# design.net
KiCad netlist of a schematic drawn in Altium Designer
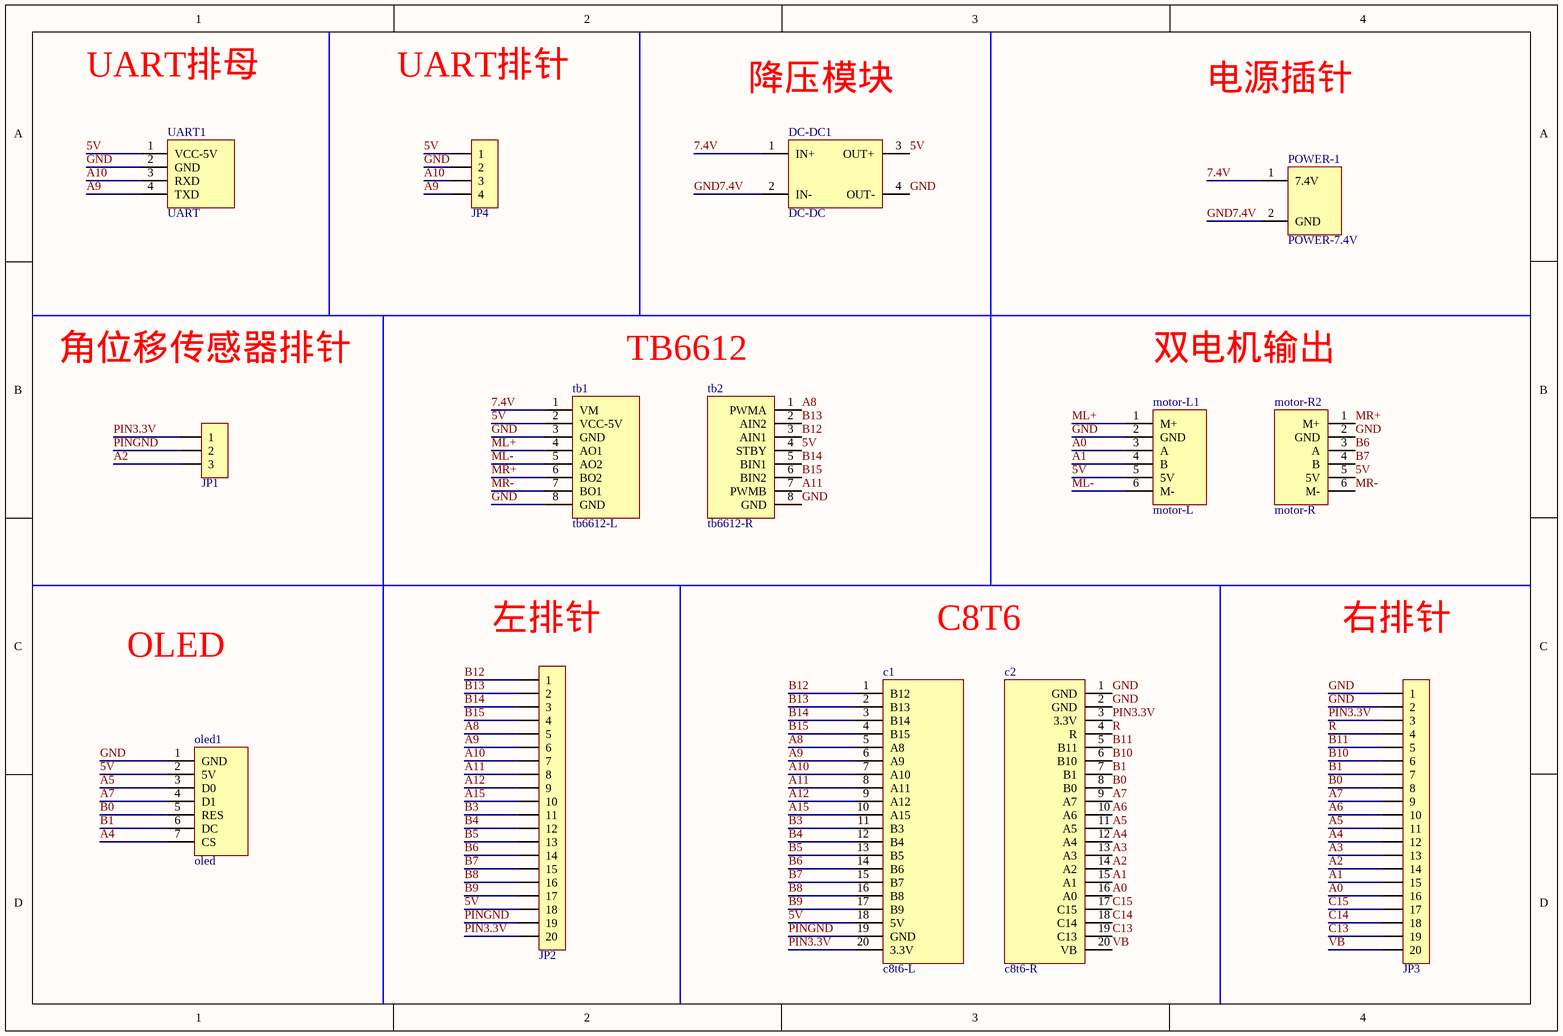
[diagram p0: 倒立摆原理图.SchDoc]

(export (version "E")
  (design (tool "Eeschema 10.0.6"))
  (components
    (comp (ref "c1") (value "c8t6-L") (footprint "HDR2.54-M-LI-20P") (libsource (lib "平衡车") (part "c8t6-L")))
    (comp (ref "c2") (value "c8t6-R") (footprint "HDR2.54-M-LI-20P") (libsource (lib "平衡车") (part "c8t6-R")))
    (comp (ref "DC-DC1") (value "DC-DC") (footprint "DC-DC") (libsource (lib "平衡车") (part "DC-DC")))
    (comp (ref "JP1")
      (value "HDR-1X3")
      (footprint "HDR2.54-LI-3P")
      (description "3P接插件")
      (libsource (lib "5.5 - 2.54mm连接器(KF2EDGK_XH2.54_2.54排针排母)") (part "Header 3"))
    )
    (comp (ref "JP2")
      (value "HDR-1X20")
      (footprint "HDR2.54-LI-20P")
      (description "20P接插件")
      (libsource (lib "5.5 - 2.54mm连接器(KF2EDGK_XH2.54_2.54排针排母)") (part "Header 20"))
    )
    (comp (ref "JP3")
      (value "HDR-1X20")
      (footprint "HDR2.54-LI-20P")
      (description "20P接插件")
      (libsource (lib "5.5 - 2.54mm连接器(KF2EDGK_XH2.54_2.54排针排母)") (part "Header 20"))
    )
    (comp (ref "JP4")
      (value "HDR-1X4")
      (footprint "HDR2.54-LI-4P")
      (description "4P接插件")
      (libsource (lib "5.5 - 2.54mm连接器(KF2EDGK_XH2.54_2.54排针排母)") (part "Header 4"))
    )
    (comp (ref "motor-L1")
      (value "motor-L")
      (footprint "HDR2.54-WI-6P")
      (libsource (lib "平衡车") (part "motor-L"))
    )
    (comp (ref "motor-R2")
      (value "motor-R")
      (footprint "HDR2.54-WI-6P")
      (libsource (lib "平衡车") (part "motor-R"))
    )
    (comp (ref "oled1") (value "oled") (footprint "HDR2.54-M-LI-7P") (libsource (lib "平衡车") (part "oled")))
    (comp (ref "POWER-1")
      (value "POWER-7.4V")
      (footprint "HDR2.54-LI-2P")
      (libsource (lib "平衡车") (part "POWER-7.4V"))
    )
    (comp (ref "tb1")
      (value "tb6612-L")
      (footprint "HDR2.54-M-LI-8P")
      (libsource (lib "平衡车") (part "tb6612-L"))
    )
    (comp (ref "tb2")
      (value "tb6612-R")
      (footprint "HDR2.54-M-LI-8P")
      (libsource (lib "平衡车") (part "tb6612-R"))
    )
    (comp (ref "UART1") (value "UART") (footprint "HDR2.54-M-LI-4P") (libsource (lib "平衡车") (part "UART")))
  )
  (nets
    (net (code "1") (name "/5V") (class "Default")
      (node (ref "DC-DC1") (pin "3") (pinfunction "OUT+_3") (pintype "passive"))
      (node (ref "JP2") (pin "18") (pinfunction "18_18") (pintype "passive"))
      (node (ref "JP4") (pin "1") (pinfunction "1_1") (pintype "passive"))
      (node (ref "UART1") (pin "1") (pinfunction "VCC-5V_1") (pintype "passive"))
      (node (ref "c1") (pin "18") (pinfunction "5V_18") (pintype "passive"))
      (node (ref "motor-L1") (pin "5") (pinfunction "5V_5") (pintype "passive"))
      (node (ref "motor-R2") (pin "5") (pinfunction "5V_5") (pintype "passive"))
      (node (ref "oled1") (pin "2") (pinfunction "5V_2") (pintype "passive"))
      (node (ref "tb1") (pin "2") (pinfunction "VCC-5V_2") (pintype "passive"))
      (node (ref "tb2") (pin "4") (pinfunction "STBY_4") (pintype "passive"))
    )
    (net (code "2") (name "/7.4V") (class "Default")
      (node (ref "DC-DC1") (pin "1") (pinfunction "IN+_1") (pintype "passive"))
      (node (ref "POWER-1") (pin "1") (pinfunction "7.4V_1") (pintype "passive"))
      (node (ref "tb1") (pin "1") (pinfunction "VM_1") (pintype "passive"))
    )
    (net (code "3") (name "/A0") (class "Default")
      (node (ref "JP3") (pin "16") (pinfunction "16_16") (pintype "passive"))
      (node (ref "c2") (pin "16") (pinfunction "A0_16") (pintype "passive"))
      (node (ref "motor-L1") (pin "3") (pinfunction "A_3") (pintype "passive"))
    )
    (net (code "4") (name "/A1") (class "Default")
      (node (ref "JP3") (pin "15") (pinfunction "15_15") (pintype "passive"))
      (node (ref "c2") (pin "15") (pinfunction "A1_15") (pintype "passive"))
      (node (ref "motor-L1") (pin "4") (pinfunction "B_4") (pintype "passive"))
    )
    (net (code "5") (name "/A2") (class "Default")
      (node (ref "JP1") (pin "3") (pinfunction "3_3") (pintype "passive"))
      (node (ref "JP3") (pin "14") (pinfunction "14_14") (pintype "passive"))
      (node (ref "c2") (pin "14") (pinfunction "A2_14") (pintype "passive"))
    )
    (net (code "6") (name "/A3") (class "Default")
      (node (ref "JP3") (pin "13") (pinfunction "13_13") (pintype "passive"))
      (node (ref "c2") (pin "13") (pinfunction "A3_13") (pintype "passive"))
    )
    (net (code "7") (name "/A4") (class "Default")
      (node (ref "JP3") (pin "12") (pinfunction "12_12") (pintype "passive"))
      (node (ref "c2") (pin "12") (pinfunction "A4_12") (pintype "passive"))
      (node (ref "oled1") (pin "7") (pinfunction "CS_7") (pintype "passive"))
    )
    (net (code "8") (name "/A5") (class "Default")
      (node (ref "JP3") (pin "11") (pinfunction "11_11") (pintype "passive"))
      (node (ref "c2") (pin "11") (pinfunction "A5_11") (pintype "passive"))
      (node (ref "oled1") (pin "3") (pinfunction "D0_3") (pintype "passive"))
    )
    (net (code "9") (name "/A6") (class "Default")
      (node (ref "JP3") (pin "10") (pinfunction "10_10") (pintype "passive"))
      (node (ref "c2") (pin "10") (pinfunction "A6_10") (pintype "passive"))
    )
    (net (code "10") (name "/A7") (class "Default")
      (node (ref "JP3") (pin "9") (pinfunction "9_9") (pintype "passive"))
      (node (ref "c2") (pin "9") (pinfunction "A7_9") (pintype "passive"))
      (node (ref "oled1") (pin "4") (pinfunction "D1_4") (pintype "passive"))
    )
    (net (code "11") (name "/A8") (class "Default")
      (node (ref "JP2") (pin "5") (pinfunction "5_5") (pintype "passive"))
      (node (ref "c1") (pin "5") (pinfunction "A8_5") (pintype "passive"))
      (node (ref "tb2") (pin "1") (pinfunction "PWMA_1") (pintype "passive"))
    )
    (net (code "12") (name "/A9") (class "Default")
      (node (ref "JP2") (pin "6") (pinfunction "6_6") (pintype "passive"))
      (node (ref "JP4") (pin "4") (pinfunction "4_4") (pintype "passive"))
      (node (ref "UART1") (pin "4") (pinfunction "TXD_4") (pintype "passive"))
      (node (ref "c1") (pin "6") (pinfunction "A9_6") (pintype "passive"))
    )
    (net (code "13") (name "/A10") (class "Default")
      (node (ref "JP2") (pin "7") (pinfunction "7_7") (pintype "passive"))
      (node (ref "JP4") (pin "3") (pinfunction "3_3") (pintype "passive"))
      (node (ref "UART1") (pin "3") (pinfunction "RXD_3") (pintype "passive"))
      (node (ref "c1") (pin "7") (pinfunction "A10_7") (pintype "passive"))
    )
    (net (code "14") (name "/A11") (class "Default")
      (node (ref "JP2") (pin "8") (pinfunction "8_8") (pintype "passive"))
      (node (ref "c1") (pin "8") (pinfunction "A11_8") (pintype "passive"))
      (node (ref "tb2") (pin "7") (pinfunction "PWMB_7") (pintype "passive"))
    )
    (net (code "15") (name "/A12") (class "Default")
      (node (ref "JP2") (pin "9") (pinfunction "9_9") (pintype "passive"))
      (node (ref "c1") (pin "9") (pinfunction "A12_9") (pintype "passive"))
    )
    (net (code "16") (name "/A15") (class "Default")
      (node (ref "JP2") (pin "10") (pinfunction "10_10") (pintype "passive"))
      (node (ref "c1") (pin "10") (pinfunction "A15_10") (pintype "passive"))
    )
    (net (code "17") (name "/B0") (class "Default")
      (node (ref "JP3") (pin "8") (pinfunction "8_8") (pintype "passive"))
      (node (ref "c2") (pin "8") (pinfunction "B0_8") (pintype "passive"))
      (node (ref "oled1") (pin "5") (pinfunction "RES_5") (pintype "passive"))
    )
    (net (code "18") (name "/B1") (class "Default")
      (node (ref "JP3") (pin "7") (pinfunction "7_7") (pintype "passive"))
      (node (ref "c2") (pin "7") (pinfunction "B1_7") (pintype "passive"))
      (node (ref "oled1") (pin "6") (pinfunction "DC_6") (pintype "passive"))
    )
    (net (code "19") (name "/B3") (class "Default")
      (node (ref "JP2") (pin "11") (pinfunction "11_11") (pintype "passive"))
      (node (ref "c1") (pin "11") (pinfunction "B3_11") (pintype "passive"))
    )
    (net (code "20") (name "/B4") (class "Default")
      (node (ref "JP2") (pin "12") (pinfunction "12_12") (pintype "passive"))
      (node (ref "c1") (pin "12") (pinfunction "B4_12") (pintype "passive"))
    )
    (net (code "21") (name "/B5") (class "Default")
      (node (ref "JP2") (pin "13") (pinfunction "13_13") (pintype "passive"))
      (node (ref "c1") (pin "13") (pinfunction "B5_13") (pintype "passive"))
    )
    (net (code "22") (name "/B6") (class "Default")
      (node (ref "JP2") (pin "14") (pinfunction "14_14") (pintype "passive"))
      (node (ref "c1") (pin "14") (pinfunction "B6_14") (pintype "passive"))
      (node (ref "motor-R2") (pin "3") (pinfunction "A_3") (pintype "passive"))
    )
    (net (code "23") (name "/B7") (class "Default")
      (node (ref "JP2") (pin "15") (pinfunction "15_15") (pintype "passive"))
      (node (ref "c1") (pin "15") (pinfunction "B7_15") (pintype "passive"))
      (node (ref "motor-R2") (pin "4") (pinfunction "B_4") (pintype "passive"))
    )
    (net (code "24") (name "/B8") (class "Default")
      (node (ref "JP2") (pin "16") (pinfunction "16_16") (pintype "passive"))
      (node (ref "c1") (pin "16") (pinfunction "B8_16") (pintype "passive"))
    )
    (net (code "25") (name "/B9") (class "Default")
      (node (ref "JP2") (pin "17") (pinfunction "17_17") (pintype "passive"))
      (node (ref "c1") (pin "17") (pinfunction "B9_17") (pintype "passive"))
    )
    (net (code "26") (name "/B10") (class "Default")
      (node (ref "JP3") (pin "6") (pinfunction "6_6") (pintype "passive"))
      (node (ref "c2") (pin "6") (pinfunction "B10_6") (pintype "passive"))
    )
    (net (code "27") (name "/B11") (class "Default")
      (node (ref "JP3") (pin "5") (pinfunction "5_5") (pintype "passive"))
      (node (ref "c2") (pin "5") (pinfunction "B11_5") (pintype "passive"))
    )
    (net (code "28") (name "/B12") (class "Default")
      (node (ref "JP2") (pin "1") (pinfunction "1_1") (pintype "passive"))
      (node (ref "c1") (pin "1") (pinfunction "B12_1") (pintype "passive"))
      (node (ref "tb2") (pin "3") (pinfunction "AIN1_3") (pintype "passive"))
    )
    (net (code "29") (name "/B13") (class "Default")
      (node (ref "JP2") (pin "2") (pinfunction "2_2") (pintype "passive"))
      (node (ref "c1") (pin "2") (pinfunction "B13_2") (pintype "passive"))
      (node (ref "tb2") (pin "2") (pinfunction "AIN2_2") (pintype "passive"))
    )
    (net (code "30") (name "/B14") (class "Default")
      (node (ref "JP2") (pin "3") (pinfunction "3_3") (pintype "passive"))
      (node (ref "c1") (pin "3") (pinfunction "B14_3") (pintype "passive"))
      (node (ref "tb2") (pin "5") (pinfunction "BIN1_5") (pintype "passive"))
    )
    (net (code "31") (name "/B15") (class "Default")
      (node (ref "JP2") (pin "4") (pinfunction "4_4") (pintype "passive"))
      (node (ref "c1") (pin "4") (pinfunction "B15_4") (pintype "passive"))
      (node (ref "tb2") (pin "6") (pinfunction "BIN2_6") (pintype "passive"))
    )
    (net (code "32") (name "/C13") (class "Default")
      (node (ref "JP3") (pin "19") (pinfunction "19_19") (pintype "passive"))
      (node (ref "c2") (pin "19") (pinfunction "C13_19") (pintype "passive"))
    )
    (net (code "33") (name "/C14") (class "Default")
      (node (ref "JP3") (pin "18") (pinfunction "18_18") (pintype "passive"))
      (node (ref "c2") (pin "18") (pinfunction "C14_18") (pintype "passive"))
    )
    (net (code "34") (name "/C15") (class "Default")
      (node (ref "JP3") (pin "17") (pinfunction "17_17") (pintype "passive"))
      (node (ref "c2") (pin "17") (pinfunction "C15_17") (pintype "passive"))
    )
    (net (code "35") (name "/GND") (class "Default")
      (node (ref "DC-DC1") (pin "4") (pinfunction "OUT-_4") (pintype "passive"))
      (node (ref "JP3") (pin "1") (pinfunction "1_1") (pintype "passive"))
      (node (ref "JP3") (pin "2") (pinfunction "2_2") (pintype "passive"))
      (node (ref "JP4") (pin "2") (pinfunction "2_2") (pintype "passive"))
      (node (ref "UART1") (pin "2") (pinfunction "GND_2") (pintype "passive"))
      (node (ref "c2") (pin "1") (pinfunction "GND_1") (pintype "passive"))
      (node (ref "c2") (pin "2") (pinfunction "GND_2") (pintype "passive"))
      (node (ref "motor-L1") (pin "2") (pinfunction "GND_2") (pintype "passive"))
      (node (ref "motor-R2") (pin "2") (pinfunction "GND_2") (pintype "passive"))
      (node (ref "oled1") (pin "1") (pinfunction "GND_1") (pintype "passive"))
      (node (ref "tb1") (pin "3") (pinfunction "GND_3") (pintype "passive"))
      (node (ref "tb1") (pin "8") (pinfunction "GND_8") (pintype "passive"))
      (node (ref "tb2") (pin "8") (pinfunction "GND_8") (pintype "passive"))
    )
    (net (code "36") (name "/GND7.4V") (class "Default")
      (node (ref "DC-DC1") (pin "2") (pinfunction "IN-_2") (pintype "passive"))
      (node (ref "POWER-1") (pin "2") (pinfunction "GND_2") (pintype "passive"))
    )
    (net (code "37") (name "/ML+") (class "Default")
      (node (ref "motor-L1") (pin "1") (pinfunction "M+_1") (pintype "passive"))
      (node (ref "tb1") (pin "4") (pinfunction "AO1_4") (pintype "passive"))
    )
    (net (code "38") (name "/ML-") (class "Default")
      (node (ref "motor-L1") (pin "6") (pinfunction "M-_6") (pintype "passive"))
      (node (ref "tb1") (pin "5") (pinfunction "AO2_5") (pintype "passive"))
    )
    (net (code "39") (name "/MR+") (class "Default")
      (node (ref "motor-R2") (pin "1") (pinfunction "M+_1") (pintype "passive"))
      (node (ref "tb1") (pin "6") (pinfunction "BO2_6") (pintype "passive"))
    )
    (net (code "40") (name "/MR-") (class "Default")
      (node (ref "motor-R2") (pin "6") (pinfunction "M-_6") (pintype "passive"))
      (node (ref "tb1") (pin "7") (pinfunction "BO1_7") (pintype "passive"))
    )
    (net (code "41") (name "/PIN3.3V") (class "Default")
      (node (ref "JP1") (pin "1") (pinfunction "1_1") (pintype "passive"))
      (node (ref "JP2") (pin "20") (pinfunction "20_20") (pintype "passive"))
      (node (ref "JP3") (pin "3") (pinfunction "3_3") (pintype "passive"))
      (node (ref "c1") (pin "20") (pinfunction "3.3V_20") (pintype "passive"))
      (node (ref "c2") (pin "3") (pinfunction "3.3V_3") (pintype "passive"))
    )
    (net (code "42") (name "/PINGND") (class "Default")
      (node (ref "JP1") (pin "2") (pinfunction "2_2") (pintype "passive"))
      (node (ref "JP2") (pin "19") (pinfunction "19_19") (pintype "passive"))
      (node (ref "c1") (pin "19") (pinfunction "GND_19") (pintype "passive"))
    )
    (net (code "43") (name "/R") (class "Default")
      (node (ref "JP3") (pin "4") (pinfunction "4_4") (pintype "passive"))
      (node (ref "c2") (pin "4") (pinfunction "R_4") (pintype "passive"))
    )
    (net (code "44") (name "/VB") (class "Default")
      (node (ref "JP3") (pin "20") (pinfunction "20_20") (pintype "passive"))
      (node (ref "c2") (pin "20") (pinfunction "VB_20") (pintype "passive"))
    )
  )
)
